# M1_Schematic.net
KiCad netlist of a schematic drawn in Altium Designer
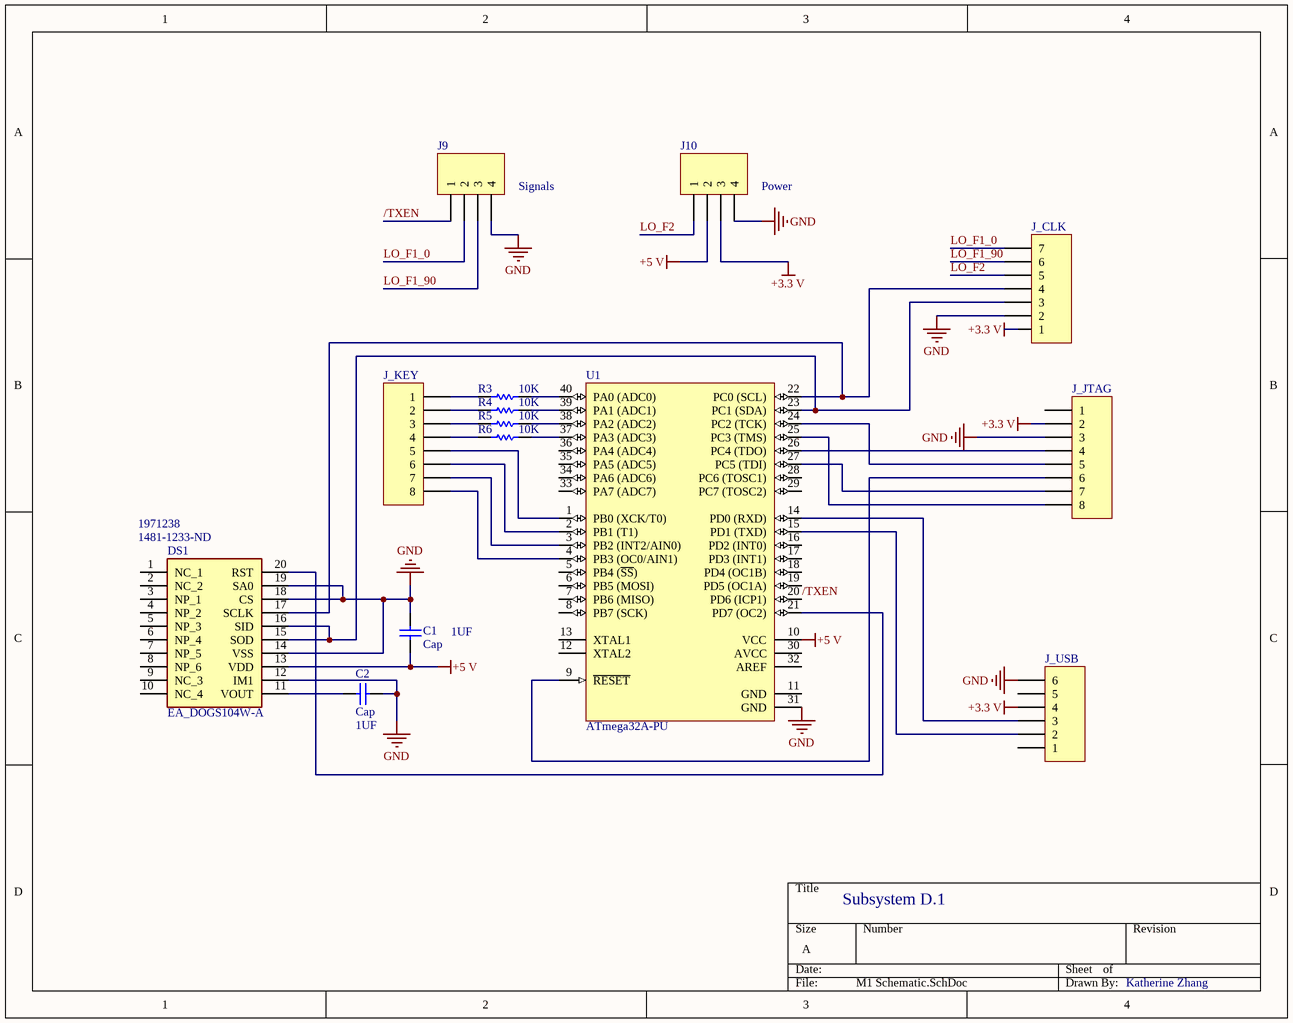
[diagram p0: M1 Schematic.SchDoc]

(export (version "E")
  (design (tool "Eeschema 10.0.6"))
  (components
    (comp (ref "C1")
      (value "Cap")
      (footprint "RADIAL-0.1")
      (description "Capacitor")
      (fields
        (field (name "MANUFACTURER PART NUMBER") "ESE105M100AC3EA")
        (field (name "ALTIUM_VALUE") "1UF")
        (field (name "PUBLISHER") "Altium Limited")
      )
      (libsource (lib "ECE295-Capacitors-TH") (part "CAP ALUM 1UF 20% 100V RADIAL"))
    )
    (comp (ref "C2")
      (value "Cap")
      (footprint "RADIAL-0.1")
      (description "Capacitor")
      (fields
        (field (name "MANUFACTURER PART NUMBER") "ESE105M100AC3EA")
        (field (name "ALTIUM_VALUE") "1UF")
        (field (name "PUBLISHER") "Altium Limited")
      )
      (libsource (lib "ECE295-Capacitors-TH") (part "CAP ALUM 1UF 20% 100V RADIAL"))
    )
    (comp (ref "DS1")
      (value "EA_DOGS104W-A")
      (footprint "DIP2540W50P254L3600H260Q20N")
      (description "LCM char. 4x10 FSTN White")
      (fields
        (field (name "MOUSER2 PART NUMBER") "790-EADOGS104W-A")
        (field (name "MANUFACTURER_PART_NUMBER") "EA DOGS104W-A")
        (field (name "SUPPLIER PART NUMBER 1") "1481-1233-ND")
        (field (name "SUPPLIER PART NUMBER 2") "1971238")
      )
      (libsource (lib "SamacSys") (part "EA_DOGS104W-A"))
    )
    (comp (ref "J9")
      (value "Signals")
      (footprint "HDR1X4")
      (description "Conn Header Vert 4POS 2.54MM")
      (fields
        (field (name "MANUFACTURER") "Sullins")
        (field (name "MANUFACTURER PART NUMBER") "PRPC004SAAN-RC")
        (field (name "PUBLISHER") "Altium Limited")
      )
      (libsource (lib "Miscellaneous Connectors") (part "Header 4"))
    )
    (comp (ref "J10")
      (value "Power")
      (footprint "HDR1X4")
      (description "Conn Header Vert 4POS 2.54MM")
      (fields
        (field (name "MANUFACTURER") "Sullins")
        (field (name "MANUFACTURER PART NUMBER") "PRPC004SAAN-RC")
        (field (name "PUBLISHER") "Altium Limited")
      )
      (libsource (lib "Miscellaneous Connectors") (part "Header 4"))
    )
    (comp (ref "J_CLK")
      (value "Header 7")
      (footprint "HDR1X7")
      (description "Female, 7C, Straight, .100\"CC; 3.20mm Tail, No Mt. 100u\" Tin; PBT, Phos Bronze, 105 C")
      (fields
        (field (name "MANUFACTURER") "Sullins")
        (field (name "MANUFACTURER PART NUMBER") "PPTC071LFBN-RC")
        (field (name "PUBLISHER") "Altium Limited")
      )
      (libsource (lib "Miscellaneous Connectors") (part "Header 7"))
    )
    (comp (ref "J_JTAG")
      (value "Header 8")
      (footprint "HDR1X8")
      (description "Conn Header Vert 8POS 2.54MM")
      (fields
        (field (name "MANUFACTURER") "Sullins")
        (field (name "MANUFACTURER PART NUMBER") "PRPC008SAAN-RC")
        (field (name "PUBLISHER") "Altium Limited")
      )
      (libsource (lib "") (part "Header 8_1"))
    )
    (comp (ref "J_KEY")
      (value "Header 8")
      (footprint "HDR1X8")
      (description "Conn Header Vert 8POS 2.54MM")
      (fields
        (field (name "MANUFACTURER") "Sullins")
        (field (name "MANUFACTURER PART NUMBER") "PRPC008SAAN-RC")
        (field (name "PUBLISHER") "Altium Limited")
      )
      (libsource (lib "Miscellaneous Connectors") (part "Header 8"))
    )
    (comp (ref "J_USB")
      (value "Header 6")
      (footprint "HDR1X6")
      (description "Conn Header .100\" Sngl Str 6POS")
      (fields
        (field (name "MANUFACTURER") "Sullins")
        (field (name "MANUFACTURER PART NUMBER") "PRPC006SAAN-RC")
        (field (name "PUBLISHER") "Altium Limited")
      )
      (libsource (lib "Miscellaneous Connectors") (part "Header 6"))
    )
    (comp (ref "R3")
      (value "10K")
      (footprint "AXIAL-0.1-RES")
      (description "Resistor")
      (fields
        (field (name "MANUFACTURER PART NUMBER") "CFR-25JB-52-10K")
        (field (name "TOLERANCE") "0.05")
        (field (name "PUBLISHER") "Altium Limited")
      )
      (libsource (lib "ECE295-Resistors-TH") (part "RES 10K OHM 5% 1/4W AXIAL"))
    )
    (comp (ref "R4")
      (value "10K")
      (footprint "AXIAL-0.1-RES")
      (description "Resistor")
      (fields
        (field (name "MANUFACTURER PART NUMBER") "CFR-25JB-52-10K")
        (field (name "TOLERANCE") "0.05")
        (field (name "PUBLISHER") "Altium Limited")
      )
      (libsource (lib "ECE295-Resistors-TH") (part "RES 10K OHM 5% 1/4W AXIAL"))
    )
    (comp (ref "R5")
      (value "10K")
      (footprint "AXIAL-0.1-RES")
      (description "Resistor")
      (fields
        (field (name "MANUFACTURER PART NUMBER") "CFR-25JB-52-10K")
        (field (name "TOLERANCE") "0.05")
        (field (name "PUBLISHER") "Altium Limited")
      )
      (libsource (lib "ECE295-Resistors-TH") (part "RES 10K OHM 5% 1/4W AXIAL"))
    )
    (comp (ref "R6")
      (value "10K")
      (footprint "AXIAL-0.1-RES")
      (description "Resistor")
      (fields
        (field (name "MANUFACTURER PART NUMBER") "CFR-25JB-52-10K")
        (field (name "TOLERANCE") "0.05")
        (field (name "PUBLISHER") "Altium Limited")
      )
      (libsource (lib "ECE295-Resistors-TH") (part "RES 10K OHM 5% 1/4W AXIAL"))
    )
    (comp (ref "U1")
      (value "ATmega32A-PU")
      (footprint "40P6")
      (fields
        (field (name "MANUFACTURER") "Microchip")
        (field (name "MANUFACTURER PART NUMBER") "ATMEGA324A-PU")
      )
      (libsource (lib "Altium Content Vault") (part "MC-8B-AT16A-IL40"))
    )
  )
  (nets
    (net (code "1") (name "+3.3 V") (class "Default")
      (node (ref "J10") (pin "3") (pinfunction "3_3") (pintype "passive"))
      (node (ref "J_CLK") (pin "1") (pinfunction "1_1") (pintype "passive"))
      (node (ref "J_JTAG") (pin "2") (pinfunction "2_2") (pintype "passive"))
      (node (ref "J_USB") (pin "4") (pinfunction "4_4") (pintype "passive"))
    )
    (net (code "2") (name "+5 V") (class "Default")
      (node (ref "C1") (pin "1") (pinfunction "1_1") (pintype "passive"))
      (node (ref "DS1") (pin "13") (pinfunction "VDD_13") (pintype "passive"))
      (node (ref "J10") (pin "2") (pinfunction "2_2") (pintype "passive"))
      (node (ref "U1") (pin "10") (pinfunction "VCC_10") (pintype "power_in"))
    )
    (net (code "3") (name "/LO_F1_0") (class "Default")
      (node (ref "J9") (pin "2") (pinfunction "2_2") (pintype "passive"))
      (node (ref "J_CLK") (pin "7") (pinfunction "7_7") (pintype "passive"))
    )
    (net (code "4") (name "/LO_F1_90") (class "Default")
      (node (ref "J9") (pin "3") (pinfunction "3_3") (pintype "passive"))
      (node (ref "J_CLK") (pin "6") (pinfunction "6_6") (pintype "passive"))
    )
    (net (code "5") (name "/LO_F2") (class "Default")
      (node (ref "J10") (pin "1") (pinfunction "1_1") (pintype "passive"))
      (node (ref "J_CLK") (pin "5") (pinfunction "5_5") (pintype "passive"))
    )
    (net (code "6") (name "/{slash}TXEN") (class "Default")
      (node (ref "J9") (pin "1") (pinfunction "1_1") (pintype "passive"))
      (node (ref "U1") (pin "20") (pinfunction "PD6_(ICP1)_20") (pintype "bidirectional"))
    )
    (net (code "7") (name "GND") (class "Default")
      (node (ref "C1") (pin "2") (pinfunction "2_2") (pintype "passive"))
      (node (ref "C2") (pin "2") (pinfunction "2_2") (pintype "passive"))
      (node (ref "DS1") (pin "12") (pinfunction "IM1_12") (pintype "passive"))
      (node (ref "DS1") (pin "14") (pinfunction "VSS_14") (pintype "passive"))
      (node (ref "DS1") (pin "18") (pinfunction "CS_18") (pintype "passive"))
      (node (ref "DS1") (pin "19") (pinfunction "SA0_19") (pintype "passive"))
      (node (ref "J10") (pin "4") (pinfunction "4_4") (pintype "passive"))
      (node (ref "J9") (pin "4") (pinfunction "4_4") (pintype "passive"))
      (node (ref "J_CLK") (pin "2") (pinfunction "2_2") (pintype "passive"))
      (node (ref "J_JTAG") (pin "3") (pinfunction "3_3") (pintype "passive"))
      (node (ref "J_USB") (pin "6") (pinfunction "6_6") (pintype "passive"))
      (node (ref "U1") (pin "31") (pinfunction "GND_31") (pintype "power_in"))
    )
    (net (code "8") (name "Net-(DS1-RST)") (class "Default")
      (node (ref "DS1") (pin "20") (pinfunction "RST_20") (pintype "passive"))
      (node (ref "U1") (pin "21") (pinfunction "PD7_(OC2)_21") (pintype "bidirectional"))
    )
    (net (code "9") (name "Net-(DS1-SCLK)") (class "Default")
      (node (ref "DS1") (pin "17") (pinfunction "SCLK_17") (pintype "passive"))
      (node (ref "J_CLK") (pin "4") (pinfunction "4_4") (pintype "passive"))
      (node (ref "U1") (pin "22") (pinfunction "PC0_(SCL)_22") (pintype "bidirectional"))
    )
    (net (code "10") (name "Net-(DS1-SID)") (class "Default")
      (node (ref "DS1") (pin "15") (pinfunction "SOD_15") (pintype "passive"))
      (node (ref "DS1") (pin "16") (pinfunction "SID_16") (pintype "passive"))
      (node (ref "J_CLK") (pin "3") (pinfunction "3_3") (pintype "passive"))
      (node (ref "U1") (pin "23") (pinfunction "PC1_(SDA)_23") (pintype "bidirectional"))
    )
    (net (code "11") (name "Net-(DS1-VOUT)") (class "Default")
      (node (ref "C2") (pin "1") (pinfunction "1_1") (pintype "passive"))
      (node (ref "DS1") (pin "11") (pinfunction "VOUT_11") (pintype "passive"))
    )
    (net (code "12") (name "Net-(J_KEY-Pad1)") (class "Default")
      (node (ref "J_KEY") (pin "1") (pinfunction "1_1") (pintype "passive"))
      (node (ref "R3") (pin "1") (pinfunction "1_1") (pintype "passive"))
    )
    (net (code "13") (name "Net-(J_KEY-Pad2)") (class "Default")
      (node (ref "J_KEY") (pin "2") (pinfunction "2_2") (pintype "passive"))
      (node (ref "R4") (pin "1") (pinfunction "1_1") (pintype "passive"))
    )
    (net (code "14") (name "Net-(J_KEY-Pad3)") (class "Default")
      (node (ref "J_KEY") (pin "3") (pinfunction "3_3") (pintype "passive"))
      (node (ref "R5") (pin "1") (pinfunction "1_1") (pintype "passive"))
    )
    (net (code "15") (name "Net-(J_KEY-Pad4)") (class "Default")
      (node (ref "J_KEY") (pin "4") (pinfunction "4_4") (pintype "passive"))
      (node (ref "R6") (pin "1") (pinfunction "1_1") (pintype "passive"))
    )
    (net (code "16") (name "Net-(U1-PA0_(ADC0))") (class "Default")
      (node (ref "R3") (pin "2") (pinfunction "2_2") (pintype "passive"))
      (node (ref "U1") (pin "40") (pinfunction "PA0_(ADC0)_40") (pintype "bidirectional"))
    )
    (net (code "17") (name "Net-(U1-PA1_(ADC1))") (class "Default")
      (node (ref "R4") (pin "2") (pinfunction "2_2") (pintype "passive"))
      (node (ref "U1") (pin "39") (pinfunction "PA1_(ADC1)_39") (pintype "bidirectional"))
    )
    (net (code "18") (name "Net-(U1-PA2_(ADC2))") (class "Default")
      (node (ref "R5") (pin "2") (pinfunction "2_2") (pintype "passive"))
      (node (ref "U1") (pin "38") (pinfunction "PA2_(ADC2)_38") (pintype "bidirectional"))
    )
    (net (code "19") (name "Net-(U1-PA3_(ADC3))") (class "Default")
      (node (ref "R6") (pin "2") (pinfunction "2_2") (pintype "passive"))
      (node (ref "U1") (pin "37") (pinfunction "PA3_(ADC3)_37") (pintype "bidirectional"))
    )
    (net (code "20") (name "Net-(U1-PB0_(XCK{slash}T0))") (class "Default")
      (node (ref "J_KEY") (pin "5") (pinfunction "5_5") (pintype "passive"))
      (node (ref "U1") (pin "1") (pinfunction "PB0_(XCK/T0)_1") (pintype "bidirectional"))
    )
    (net (code "21") (name "Net-(U1-PB1_(T1))") (class "Default")
      (node (ref "J_KEY") (pin "6") (pinfunction "6_6") (pintype "passive"))
      (node (ref "U1") (pin "2") (pinfunction "PB1_(T1)_2") (pintype "bidirectional"))
    )
    (net (code "22") (name "Net-(U1-PB2_(INT2{slash}AIN0))") (class "Default")
      (node (ref "J_KEY") (pin "7") (pinfunction "7_7") (pintype "passive"))
      (node (ref "U1") (pin "3") (pinfunction "PB2_(INT2/AIN0)_3") (pintype "bidirectional"))
    )
    (net (code "23") (name "Net-(U1-PB3_(OC0{slash}AIN1))") (class "Default")
      (node (ref "J_KEY") (pin "8") (pinfunction "8_8") (pintype "passive"))
      (node (ref "U1") (pin "4") (pinfunction "PB3_(OC0/AIN1)_4") (pintype "bidirectional"))
    )
    (net (code "24") (name "Net-(U1-PC2_(TCK))") (class "Default")
      (node (ref "J_JTAG") (pin "5") (pinfunction "5_5") (pintype "passive"))
      (node (ref "U1") (pin "24") (pinfunction "PC2_(TCK)_24") (pintype "bidirectional"))
    )
    (net (code "25") (name "Net-(U1-PC3_(TMS))") (class "Default")
      (node (ref "J_JTAG") (pin "8") (pinfunction "8_8") (pintype "passive"))
      (node (ref "U1") (pin "25") (pinfunction "PC3_(TMS)_25") (pintype "bidirectional"))
    )
    (net (code "26") (name "Net-(U1-PC4_(TDO))") (class "Default")
      (node (ref "J_JTAG") (pin "4") (pinfunction "4_4") (pintype "passive"))
      (node (ref "U1") (pin "26") (pinfunction "PC4_(TDO)_26") (pintype "bidirectional"))
    )
    (net (code "27") (name "Net-(U1-PC5_(TDI))") (class "Default")
      (node (ref "J_JTAG") (pin "7") (pinfunction "7_7") (pintype "passive"))
      (node (ref "U1") (pin "27") (pinfunction "PC5_(TDI)_27") (pintype "bidirectional"))
    )
    (net (code "28") (name "Net-(U1-PD0_(RXD))") (class "Default")
      (node (ref "J_USB") (pin "3") (pinfunction "3_3") (pintype "passive"))
      (node (ref "U1") (pin "14") (pinfunction "PD0_(RXD)_14") (pintype "bidirectional"))
    )
    (net (code "29") (name "Net-(U1-PD1_(TXD))") (class "Default")
      (node (ref "J_USB") (pin "2") (pinfunction "2_2") (pintype "passive"))
      (node (ref "U1") (pin "15") (pinfunction "PD1_(TXD)_15") (pintype "bidirectional"))
    )
    (net (code "30") (name "Net-(U1-~{RESET})") (class "Default")
      (node (ref "J_JTAG") (pin "6") (pinfunction "6_6") (pintype "passive"))
      (node (ref "U1") (pin "9") (pinfunction "~{RESET}_9") (pintype "input"))
    )
    (net (code "31") (name "unconnected-(DS1-NC_1-Pad1)") (class "Default")
      (node (ref "DS1") (pin "1") (pinfunction "NC_1_1") (pintype "passive"))
    )
    (net (code "32") (name "unconnected-(DS1-NC_2-Pad2)") (class "Default")
      (node (ref "DS1") (pin "2") (pinfunction "NC_2_2") (pintype "passive"))
    )
    (net (code "33") (name "unconnected-(DS1-NC_3-Pad9)") (class "Default")
      (node (ref "DS1") (pin "9") (pinfunction "NC_3_9") (pintype "passive"))
    )
    (net (code "34") (name "unconnected-(DS1-NC_4-Pad10)") (class "Default")
      (node (ref "DS1") (pin "10") (pinfunction "NC_4_10") (pintype "passive"))
    )
    (net (code "35") (name "unconnected-(DS1-NP_1-Pad3)") (class "Default")
      (node (ref "DS1") (pin "3") (pinfunction "NP_1_3") (pintype "passive"))
    )
    (net (code "36") (name "unconnected-(DS1-NP_2-Pad4)") (class "Default")
      (node (ref "DS1") (pin "4") (pinfunction "NP_2_4") (pintype "passive"))
    )
    (net (code "37") (name "unconnected-(DS1-NP_3-Pad5)") (class "Default")
      (node (ref "DS1") (pin "5") (pinfunction "NP_3_5") (pintype "passive"))
    )
    (net (code "38") (name "unconnected-(DS1-NP_4-Pad6)") (class "Default")
      (node (ref "DS1") (pin "6") (pinfunction "NP_4_6") (pintype "passive"))
    )
    (net (code "39") (name "unconnected-(DS1-NP_5-Pad7)") (class "Default")
      (node (ref "DS1") (pin "7") (pinfunction "NP_5_7") (pintype "passive"))
    )
    (net (code "40") (name "unconnected-(DS1-NP_6-Pad8)") (class "Default")
      (node (ref "DS1") (pin "8") (pinfunction "NP_6_8") (pintype "passive"))
    )
    (net (code "41") (name "unconnected-(J_JTAG-Pad1)") (class "Default")
      (node (ref "J_JTAG") (pin "1") (pinfunction "1_1") (pintype "passive"))
    )
    (net (code "42") (name "unconnected-(J_USB-Pad1)") (class "Default")
      (node (ref "J_USB") (pin "1") (pinfunction "1_1") (pintype "passive"))
    )
    (net (code "43") (name "unconnected-(J_USB-Pad5)") (class "Default")
      (node (ref "J_USB") (pin "5") (pinfunction "5_5") (pintype "passive"))
    )
    (net (code "44") (name "unconnected-(U1-AREF-Pad32)") (class "Default")
      (node (ref "U1") (pin "32") (pinfunction "AREF_32") (pintype "power_in"))
    )
    (net (code "45") (name "unconnected-(U1-AVCC-Pad30)") (class "Default")
      (node (ref "U1") (pin "30") (pinfunction "AVCC_30") (pintype "power_in"))
    )
    (net (code "46") (name "unconnected-(U1-GND-Pad11)") (class "Default")
      (node (ref "U1") (pin "11") (pinfunction "GND_11") (pintype "power_in"))
    )
    (net (code "47") (name "unconnected-(U1-PA4_(ADC4)-Pad36)") (class "Default")
      (node (ref "U1") (pin "36") (pinfunction "PA4_(ADC4)_36") (pintype "bidirectional"))
    )
    (net (code "48") (name "unconnected-(U1-PA5_(ADC5)-Pad35)") (class "Default")
      (node (ref "U1") (pin "35") (pinfunction "PA5_(ADC5)_35") (pintype "bidirectional"))
    )
    (net (code "49") (name "unconnected-(U1-PA6_(ADC6)-Pad34)") (class "Default")
      (node (ref "U1") (pin "34") (pinfunction "PA6_(ADC6)_34") (pintype "bidirectional"))
    )
    (net (code "50") (name "unconnected-(U1-PA7_(ADC7)-Pad33)") (class "Default")
      (node (ref "U1") (pin "33") (pinfunction "PA7_(ADC7)_33") (pintype "bidirectional"))
    )
    (net (code "51") (name "unconnected-(U1-PB4_(~{SS})-Pad5)") (class "Default")
      (node (ref "U1") (pin "5") (pinfunction "PB4_(~{SS})_5") (pintype "bidirectional"))
    )
    (net (code "52") (name "unconnected-(U1-PB5_(MOSI)-Pad6)") (class "Default")
      (node (ref "U1") (pin "6") (pinfunction "PB5_(MOSI)_6") (pintype "bidirectional"))
    )
    (net (code "53") (name "unconnected-(U1-PB6_(MISO)-Pad7)") (class "Default")
      (node (ref "U1") (pin "7") (pinfunction "PB6_(MISO)_7") (pintype "bidirectional"))
    )
    (net (code "54") (name "unconnected-(U1-PB7_(SCK)-Pad8)") (class "Default")
      (node (ref "U1") (pin "8") (pinfunction "PB7_(SCK)_8") (pintype "bidirectional"))
    )
    (net (code "55") (name "unconnected-(U1-PC6_(TOSC1)-Pad28)") (class "Default")
      (node (ref "U1") (pin "28") (pinfunction "PC6_(TOSC1)_28") (pintype "bidirectional"))
    )
    (net (code "56") (name "unconnected-(U1-PC7_(TOSC2)-Pad29)") (class "Default")
      (node (ref "U1") (pin "29") (pinfunction "PC7_(TOSC2)_29") (pintype "bidirectional"))
    )
    (net (code "57") (name "unconnected-(U1-PD2_(INT0)-Pad16)") (class "Default")
      (node (ref "U1") (pin "16") (pinfunction "PD2_(INT0)_16") (pintype "bidirectional"))
    )
    (net (code "58") (name "unconnected-(U1-PD3_(INT1)-Pad17)") (class "Default")
      (node (ref "U1") (pin "17") (pinfunction "PD3_(INT1)_17") (pintype "bidirectional"))
    )
    (net (code "59") (name "unconnected-(U1-PD4_(OC1B)-Pad18)") (class "Default")
      (node (ref "U1") (pin "18") (pinfunction "PD4_(OC1B)_18") (pintype "bidirectional"))
    )
    (net (code "60") (name "unconnected-(U1-PD5_(OC1A)-Pad19)") (class "Default")
      (node (ref "U1") (pin "19") (pinfunction "PD5_(OC1A)_19") (pintype "bidirectional"))
    )
    (net (code "61") (name "unconnected-(U1-XTAL1-Pad13)") (class "Default")
      (node (ref "U1") (pin "13") (pinfunction "XTAL1_13") (pintype "passive"))
    )
    (net (code "62") (name "unconnected-(U1-XTAL2-Pad12)") (class "Default")
      (node (ref "U1") (pin "12") (pinfunction "XTAL2_12") (pintype "passive"))
    )
  )
)
